# TEST-MODULE.net
KiCad netlist of a schematic drawn in Altium Designer
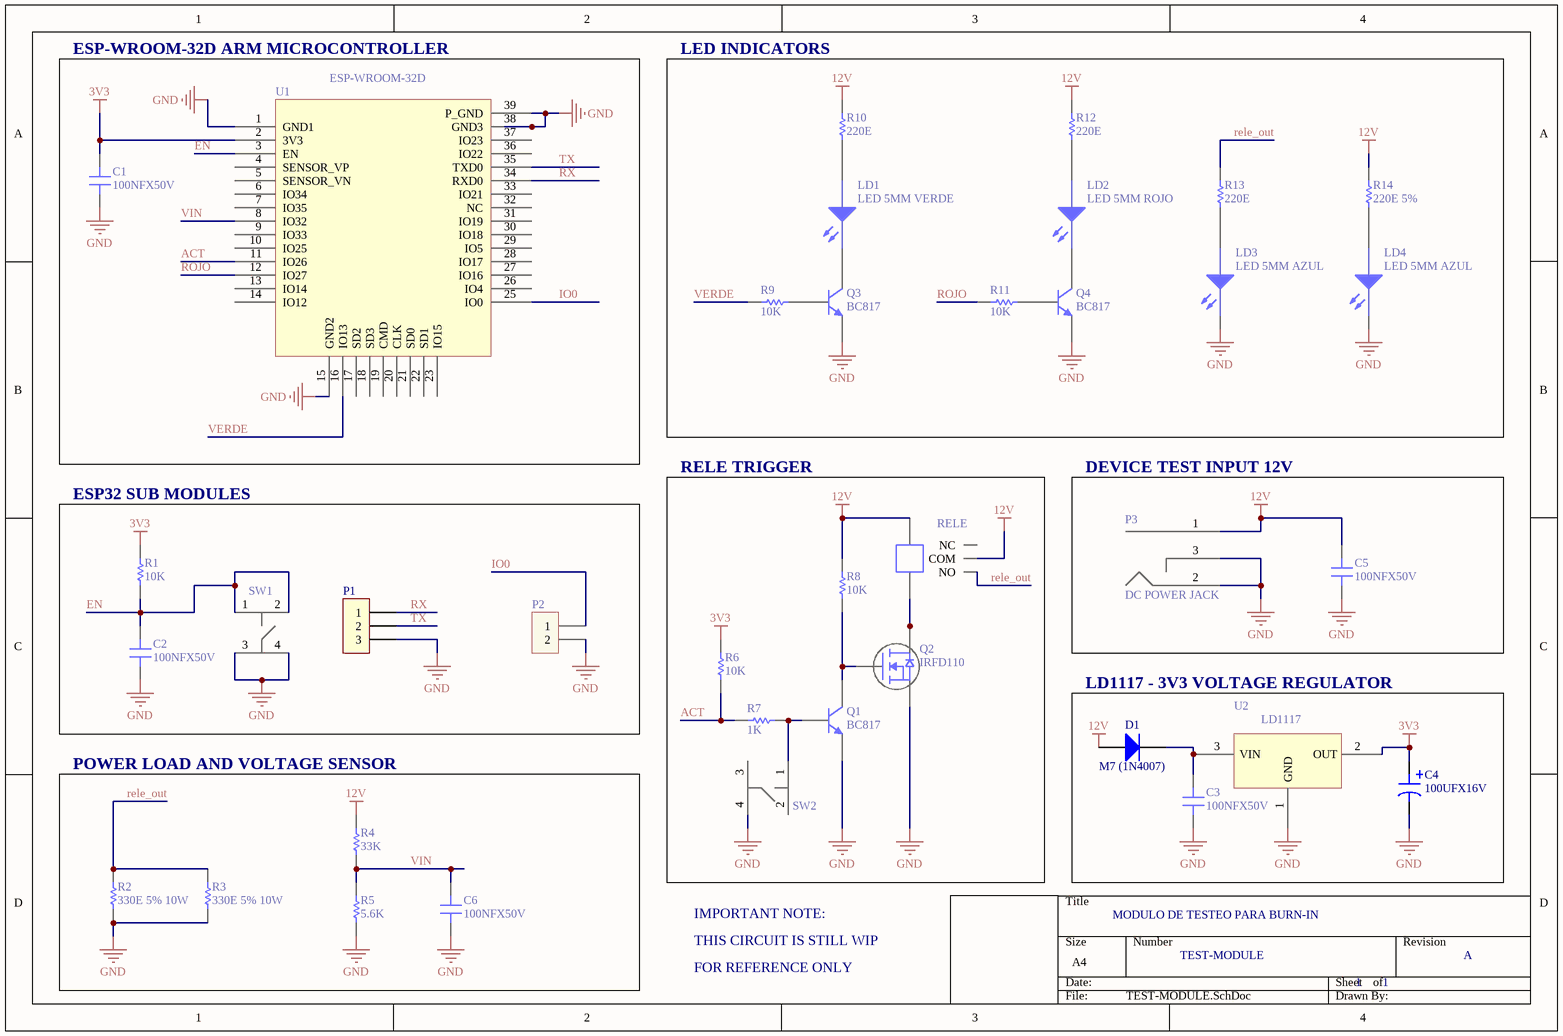
[diagram p0: TEST-MODULE.SchDoc]

(export (version "E")
  (design (tool "Eeschema 10.0.6"))
  (components
    (comp (ref "C1")
      (value "100NFX50V")
      (footprint "CAP.SMD.0805")
      (description "100NFX50V X7R 10% CER.MULT. SMD 0805")
      (libsource (lib "Libreria-Capacitores") (part "Capacitor 100NFX50V X7R 10% CER.MULT. SMD 0805"))
    )
    (comp (ref "C2")
      (value "100NFX50V")
      (footprint "CAP.SMD.0805")
      (description "100NFX50V X7R 10% CER.MULT. SMD 0805")
      (libsource (lib "Libreria-Capacitores") (part "Capacitor 100NFX50V X7R 10% CER.MULT. SMD 0805"))
    )
    (comp (ref "C3")
      (value "100NFX50V")
      (footprint "CAP.SMD.0805")
      (description "100NFX50V X7R 10% CER.MULT. SMD 0805")
      (libsource (lib "Libreria-Capacitores") (part "Capacitor 100NFX50V X7R 10% CER.MULT. SMD 0805"))
    )
    (comp (ref "C4")
      (value "100UFX16V")
      (footprint "CAP-ELEC-SMD")
      (description "100UFX16V 20%. 6.3x5.3 ELE.RAD.SMD [R=]")
      (libsource (lib "Libreria-Capacitores") (part "Capacitor Electrolitico SMD 100UFX16V 20%. 6.3x5.3 ELE.RAD.SMD [R=]"))
    )
    (comp (ref "C5")
      (value "100NFX50V")
      (footprint "CAP.SMD.0805")
      (description "100NFX50V X7R 10% CER.MULT. SMD 0805")
      (libsource (lib "Libreria-Capacitores") (part "Capacitor 100NFX50V X7R 10% CER.MULT. SMD 0805"))
    )
    (comp (ref "C6")
      (value "100NFX50V")
      (footprint "CAP.SMD.0805")
      (description "100NFX50V X7R 10% CER.MULT. SMD 0805")
      (libsource (lib "Libreria-Capacitores") (part "Capacitor 100NFX50V X7R 10% CER.MULT. SMD 0805"))
    )
    (comp (ref "D1")
      (value "M7 (1N4007)")
      (footprint "Diode-SMD-SMA")
      (description "M7 DIODO 1A 1000V SMD-SMA (1N4007) XYG")
      (libsource (lib "Libreria-Diodos") (part "Diodo M7 DIODO 1A 1000V SMD-SMA (1N4007) XYG"))
    )
    (comp (ref "LD1")
      (value "LED 5MM VERDE")
      (footprint "LED-5MM-ALTO-9-VERDE")
      (description "LED 5MM VERDE ALTO 9")
      (libsource (lib "Libreria-LEDs") (part "LED 5MM VERDE ALTO 9"))
    )
    (comp (ref "LD2")
      (value "LED 5MM ROJO")
      (footprint "LED-5MM-ALTO-9-ROJO")
      (description "LED 5MM ROJO ALTO 9")
      (libsource (lib "Libreria-LEDs") (part "LED 5MM ROJO ALTO 9"))
    )
    (comp (ref "LD3")
      (value "LED 5MM AZUL")
      (footprint "LED-5MM-ALTO-9-AZUL")
      (description "LED 5MM AZUL ALTO 9")
      (libsource (lib "Libreria-LEDs") (part "LED 5MM AZUL ALTO 9"))
    )
    (comp (ref "LD4")
      (value "LED 5MM AZUL")
      (footprint "LED-5MM-ALTO-9-AZUL")
      (description "LED 5MM AZUL ALTO 9")
      (libsource (lib "Libreria-LEDs") (part "LED 5MM AZUL ALTO 9"))
    )
    (comp (ref "P1")
      (value "IDC-MA-THT-1X3-P2.54MM-L11")
      (footprint "IDC-MA-THT-1X3-P2.54MM-L11")
      (libsource (lib "Libreria-Conectores") (part "IDC-MA-THT-1X3-P2.54MM-L11"))
    )
    (comp (ref "P2")
      (value "IDC-MA-THT-1X2-P2.54MM-L11")
      (footprint "IDC-MA-THT-1X2-P2.54MM-L11")
      (libsource (lib "Libreria-Conectores") (part "IDC-MA-THT-1X2-P2.54MM-L11"))
    )
    (comp (ref "P3")
      (value "DC POWER JACK")
      (footprint "VAR-DC-JACK - VERT")
      (description "DC POWER JACK VERTICAL 2MM")
      (libsource (lib "Libreria-Varios") (part "DC POWER JACK VERTICAL 2MM"))
    )
    (comp (ref "Q1")
      (value "BC817")
      (footprint "NPN.SMD.SOT23")
      (description "BC817-40 TRA.NPN 45V0.5A 0.25W SOT23")
      (libsource (lib "Libreria-Transistores") (part "Transistor BC817-40 TRA.NPN 45V0.5A 0.25W SOT23"))
    )
    (comp (ref "Q2")
      (value "IRFD110")
      (footprint "TRA-IRFD110")
      (description "Transistor MOSFET N IRFD110")
      (libsource (lib "Libreria-Transistores") (part "Transistor MOSFET N IRFD110"))
    )
    (comp (ref "Q3")
      (value "BC817")
      (footprint "NPN.SMD.SOT23")
      (description "BC817-40 TRA.NPN 45V0.5A 0.25W SOT23")
      (libsource (lib "Libreria-Transistores") (part "Transistor BC817-40 TRA.NPN 45V0.5A 0.25W SOT23"))
    )
    (comp (ref "Q4")
      (value "BC817")
      (footprint "NPN.SMD.SOT23")
      (description "BC817-40 TRA.NPN 45V0.5A 0.25W SOT23")
      (libsource (lib "Libreria-Transistores") (part "Transistor BC817-40 TRA.NPN 45V0.5A 0.25W SOT23"))
    )
    (comp (ref "R1")
      (value "10K")
      (footprint "RES.SMD.103")
      (description "10K 5% 0805 1/8W RES.SMD")
      (libsource (lib "Libreria-Resistencias") (part "Resistencia 10K 5% 0805 1/8W"))
    )
    (comp (ref "R2")
      (value "330E 5% 10W")
      (footprint "RES-CERAMICA-10W")
      (description "Resistencia Ceramica 330E 5% 10W SE15 RES.CEM")
      (libsource (lib "Libreria-Resistencias") (part "Resistencia Ceramica 330E 5% 10W SE15 RES.CEM"))
    )
    (comp (ref "R3")
      (value "330E 5% 10W")
      (footprint "RES-CERAMICA-10W")
      (description "Resistencia Ceramica 330E 5% 10W SE15 RES.CEM")
      (libsource (lib "Libreria-Resistencias") (part "Resistencia Ceramica 330E 5% 10W SE15 RES.CEM"))
    )
    (comp (ref "R4")
      (value "33K")
      (footprint "RES.SMD.333")
      (description "33K 5% 0805 1/8W RES.SMD")
      (libsource (lib "Libreria-Resistencias") (part "Resistencia 33K 5% 0805 1/8W"))
    )
    (comp (ref "R5")
      (value "5.6K")
      (footprint "RES.SMD.562")
      (description "5.6K 5% 0805 1/8W RES.SMD")
      (libsource (lib "Libreria-Resistencias") (part "Resistencia 5.6K 5% 0805 1/8W"))
    )
    (comp (ref "R6")
      (value "10K")
      (footprint "RES.SMD.103")
      (description "10K 5% 0805 1/8W RES.SMD")
      (libsource (lib "Libreria-Resistencias") (part "Resistencia 10K 5% 0805 1/8W"))
    )
    (comp (ref "R7")
      (value "1K")
      (footprint "RES.SMD.102")
      (description "1K 5% 0805 1/8W RES.SMD")
      (libsource (lib "Libreria-Resistencias") (part "Resistencia 1K 5% 0805 1/8W"))
    )
    (comp (ref "R8")
      (value "10K")
      (footprint "RES.SMD.103")
      (description "10K 5% 0805 1/8W RES.SMD")
      (libsource (lib "Libreria-Resistencias") (part "Resistencia 10K 5% 0805 1/8W"))
    )
    (comp (ref "R9")
      (value "10K")
      (footprint "RES.SMD.103")
      (description "10K 5% 0805 1/8W RES.SMD")
      (libsource (lib "Libreria-Resistencias") (part "Resistencia 10K 5% 0805 1/8W"))
    )
    (comp (ref "R10")
      (value "220E")
      (footprint "RES.SMD.221")
      (description "220E 5% 0805 1/8W RES.SMD")
      (libsource (lib "Libreria-Resistencias") (part "Resistencia 220E 5% 0805 1/8W"))
    )
    (comp (ref "R11")
      (value "10K")
      (footprint "RES.SMD.103")
      (description "10K 5% 0805 1/8W RES.SMD")
      (libsource (lib "Libreria-Resistencias") (part "Resistencia 10K 5% 0805 1/8W"))
    )
    (comp (ref "R12")
      (value "220E")
      (footprint "RES.SMD.221")
      (description "220E 5% 0805 1/8W RES.SMD")
      (libsource (lib "Libreria-Resistencias") (part "Resistencia 220E 5% 0805 1/8W"))
    )
    (comp (ref "R13")
      (value "220E")
      (footprint "RES.SMD.221")
      (description "220E 5% 0805 1/8W RES.SMD")
      (libsource (lib "Libreria-Resistencias") (part "Resistencia 220E 5% 0805 1/8W"))
    )
    (comp (ref "R14")
      (value "220E 5%")
      (footprint "RES.SMD.221")
      (description "220E 5% 0805 1/8W RES.SMD")
      (libsource (lib "Libreria-Resistencias") (part "Resistencia 220E 5% 0805 1/8W"))
    )
    (comp (ref "RELE")
      (value "Relay simple inversor 12V 12A")
      (footprint "RELAY 12V 12A CHICO")
      (libsource (lib "Libreria-Varios") (part "VAR-RELE-12V Relay simple inversor chico 12V 12A"))
    )
    (comp (ref "SW1")
      (value "TACT-SWITCH-THT-4C-06X06(5MM)")
      (footprint "TACT-SWITCH-THT-4C-06X06-5MM")
      (libsource (lib "Libreria-Switches") (part "TACT-SWITCH-THT-4C-06X06(5MM)"))
    )
    (comp (ref "SW2")
      (value "TACT-SWITCH-THT-4C-06X06(13MM)-JIANFU")
      (footprint "TACT-SWITCH-THT-4C-06X06-13MM")
      (libsource (lib "Libreria-Switches") (part "TACT-SWITCH-THT-4C-06X06(13MM)-JIANFU"))
    )
    (comp (ref "U1")
      (value "ESP32-WROOM-32D")
      (footprint "ESP32-WROOM-32D")
      (libsource (lib "Libreria-Semiconductores") (part "ESP32-WROOM-32D"))
    )
    (comp (ref "U2")
      (value "LD1117S33TR SMD DPAK 0.8A 3.3V LDO LINEAR REGULATOR")
      (footprint "DPAK")
      (libsource (lib "Libreria-Semiconductores") (part "LD1117S33TR SMD DPAK 0.8A 3.3V LDO LINEAR REGULATOR"))
    )
  )
  (nets
    (net (code "1") (name "/ACT") (class "Default")
      (node (ref "R6") (pin "1") (pinfunction "1_1") (pintype "passive"))
      (node (ref "R7") (pin "1") (pinfunction "1_1") (pintype "passive"))
      (node (ref "U1") (pin "11") (pinfunction "IO26_11") (pintype "passive"))
    )
    (net (code "2") (name "/EN") (class "Default")
      (node (ref "C2") (pin "2") (pinfunction "2_2") (pintype "passive"))
      (node (ref "R1") (pin "1") (pinfunction "1_1") (pintype "passive"))
      (node (ref "SW1") (pin "1") (pinfunction "1_1") (pintype "passive"))
      (node (ref "SW1") (pin "2") (pinfunction "2_2") (pintype "passive"))
      (node (ref "U1") (pin "3") (pinfunction "EN_3") (pintype "passive"))
    )
    (net (code "3") (name "/IO0") (class "Default")
      (node (ref "P2") (pin "1") (pinfunction "1_1") (pintype "passive"))
      (node (ref "U1") (pin "25") (pinfunction "IO0_25") (pintype "passive"))
    )
    (net (code "4") (name "/ROJO") (class "Default")
      (node (ref "R11") (pin "2") (pinfunction "2_2") (pintype "passive"))
      (node (ref "U1") (pin "12") (pinfunction "IO27_12") (pintype "passive"))
    )
    (net (code "5") (name "/RX") (class "Default")
      (node (ref "P1") (pin "1") (pinfunction "1_1") (pintype "passive"))
      (node (ref "U1") (pin "34") (pinfunction "RXD0_34") (pintype "passive"))
    )
    (net (code "6") (name "/TX") (class "Default")
      (node (ref "P1") (pin "2") (pinfunction "2_2") (pintype "passive"))
      (node (ref "U1") (pin "35") (pinfunction "TXD0_35") (pintype "passive"))
    )
    (net (code "7") (name "/VERDE") (class "Default")
      (node (ref "R9") (pin "1") (pinfunction "1_1") (pintype "passive"))
      (node (ref "U1") (pin "16") (pinfunction "IO13_16") (pintype "passive"))
    )
    (net (code "8") (name "/VIN") (class "Default")
      (node (ref "C6") (pin "2") (pinfunction "2_2") (pintype "passive"))
      (node (ref "R4") (pin "1") (pinfunction "1_1") (pintype "passive"))
      (node (ref "R5") (pin "2") (pinfunction "2_2") (pintype "passive"))
      (node (ref "U1") (pin "8") (pinfunction "IO32_8") (pintype "passive"))
    )
    (net (code "9") (name "/rele_out") (class "Default")
      (node (ref "R13") (pin "2") (pinfunction "2_2") (pintype "passive"))
      (node (ref "R2") (pin "2") (pinfunction "2_2") (pintype "passive"))
      (node (ref "R3") (pin "2") (pinfunction "2_2") (pintype "passive"))
      (node (ref "RELE") (pin "4") (pinfunction "NO_4") (pintype "passive"))
    )
    (net (code "10") (name "3V3") (class "Default")
      (node (ref "C1") (pin "2") (pinfunction "2_2") (pintype "passive"))
      (node (ref "C4") (pin "2") (pinfunction "2_2") (pintype "passive"))
      (node (ref "R1") (pin "2") (pinfunction "2_2") (pintype "passive"))
      (node (ref "R6") (pin "2") (pinfunction "2_2") (pintype "passive"))
      (node (ref "U1") (pin "2") (pinfunction "3V3_2") (pintype "passive"))
      (node (ref "U2") (pin "2") (pinfunction "OUT_2") (pintype "passive"))
    )
    (net (code "11") (name "12V") (class "Default")
      (node (ref "C5") (pin "2") (pinfunction "2_2") (pintype "passive"))
      (node (ref "D1") (pin "A") (pinfunction "A_A") (pintype "passive"))
      (node (ref "P3") (pin "1") (pinfunction "1_1") (pintype "passive"))
      (node (ref "R10") (pin "2") (pinfunction "2_2") (pintype "passive"))
      (node (ref "R12") (pin "2") (pinfunction "2_2") (pintype "passive"))
      (node (ref "R14") (pin "2") (pinfunction "2_2") (pintype "passive"))
      (node (ref "R4") (pin "2") (pinfunction "2_2") (pintype "passive"))
      (node (ref "R8") (pin "2") (pinfunction "2_2") (pintype "passive"))
      (node (ref "RELE") (pin "1") (pinfunction "1_1") (pintype "passive"))
      (node (ref "RELE") (pin "3") (pinfunction "COM_3") (pintype "passive"))
    )
    (net (code "12") (name "GND") (class "Default")
      (node (ref "C1") (pin "1") (pinfunction "1_1") (pintype "passive"))
      (node (ref "C2") (pin "1") (pinfunction "1_1") (pintype "passive"))
      (node (ref "C3") (pin "1") (pinfunction "1_1") (pintype "passive"))
      (node (ref "C4") (pin "1") (pinfunction "1_1") (pintype "passive"))
      (node (ref "C5") (pin "1") (pinfunction "1_1") (pintype "passive"))
      (node (ref "C6") (pin "1") (pinfunction "1_1") (pintype "passive"))
      (node (ref "LD3") (pin "K") (pinfunction "KB_K") (pintype "passive"))
      (node (ref "LD4") (pin "K") (pinfunction "KB_K") (pintype "passive"))
      (node (ref "P1") (pin "3") (pinfunction "3_3") (pintype "passive"))
      (node (ref "P2") (pin "2") (pinfunction "2_2") (pintype "passive"))
      (node (ref "P3") (pin "2") (pinfunction "2_2") (pintype "passive"))
      (node (ref "P3") (pin "3") (pinfunction "3_3") (pintype "passive"))
      (node (ref "Q1") (pin "2") (pinfunction "E_2") (pintype "passive"))
      (node (ref "Q2") (pin "4") (pinfunction "4_4") (pintype "passive"))
      (node (ref "Q3") (pin "2") (pinfunction "E_2") (pintype "passive"))
      (node (ref "Q4") (pin "2") (pinfunction "E_2") (pintype "passive"))
      (node (ref "R2") (pin "1") (pinfunction "1_1") (pintype "passive"))
      (node (ref "R3") (pin "1") (pinfunction "1_1") (pintype "passive"))
      (node (ref "R5") (pin "1") (pinfunction "1_1") (pintype "passive"))
      (node (ref "SW1") (pin "3") (pinfunction "3_3") (pintype "passive"))
      (node (ref "SW1") (pin "4") (pinfunction "4_4") (pintype "passive"))
      (node (ref "SW2") (pin "4") (pinfunction "4_4") (pintype "passive"))
      (node (ref "U1") (pin "1") (pinfunction "GND1_1") (pintype "passive"))
      (node (ref "U1") (pin "15") (pinfunction "GND2_15") (pintype "passive"))
      (node (ref "U1") (pin "38") (pinfunction "GND3_38") (pintype "passive"))
      (node (ref "U1") (pin "39") (pinfunction "P_GND_39") (pintype "passive"))
      (node (ref "U2") (pin "1") (pinfunction "GND_1") (pintype "passive"))
    )
    (net (code "13") (name "Net-(LD1-AB)") (class "Default")
      (node (ref "LD1") (pin "A") (pinfunction "AB_A") (pintype "passive"))
      (node (ref "R10") (pin "1") (pinfunction "1_1") (pintype "passive"))
    )
    (net (code "14") (name "Net-(LD1-KB)") (class "Default")
      (node (ref "LD1") (pin "K") (pinfunction "KB_K") (pintype "passive"))
      (node (ref "Q3") (pin "3") (pinfunction "C_3") (pintype "passive"))
    )
    (net (code "15") (name "Net-(LD2-AB)") (class "Default")
      (node (ref "LD2") (pin "A") (pinfunction "AB_A") (pintype "passive"))
      (node (ref "R12") (pin "1") (pinfunction "1_1") (pintype "passive"))
    )
    (net (code "16") (name "Net-(LD2-KB)") (class "Default")
      (node (ref "LD2") (pin "K") (pinfunction "KB_K") (pintype "passive"))
      (node (ref "Q4") (pin "3") (pinfunction "C_3") (pintype "passive"))
    )
    (net (code "17") (name "Net-(LD3-AB)") (class "Default")
      (node (ref "LD3") (pin "A") (pinfunction "AB_A") (pintype "passive"))
      (node (ref "R13") (pin "1") (pinfunction "1_1") (pintype "passive"))
    )
    (net (code "18") (name "Net-(LD4-AB)") (class "Default")
      (node (ref "LD4") (pin "A") (pinfunction "AB_A") (pintype "passive"))
      (node (ref "R14") (pin "1") (pinfunction "1_1") (pintype "passive"))
    )
    (net (code "19") (name "Net-(Q1-B)") (class "Default")
      (node (ref "Q1") (pin "1") (pinfunction "B_1") (pintype "passive"))
      (node (ref "R7") (pin "2") (pinfunction "2_2") (pintype "passive"))
      (node (ref "SW2") (pin "1") (pinfunction "1_1") (pintype "passive"))
    )
    (net (code "20") (name "Net-(Q1-C)") (class "Default")
      (node (ref "Q1") (pin "3") (pinfunction "C_3") (pintype "passive"))
      (node (ref "Q2") (pin "3") (pinfunction "3_3") (pintype "passive"))
      (node (ref "R8") (pin "1") (pinfunction "1_1") (pintype "passive"))
    )
    (net (code "21") (name "Net-(Q2-Pad1)") (class "Default")
      (node (ref "Q2") (pin "1") (pinfunction "1_1") (pintype "passive"))
      (node (ref "Q2") (pin "2") (pinfunction "2_2") (pintype "passive"))
      (node (ref "RELE") (pin "2") (pinfunction "2_2") (pintype "passive"))
    )
    (net (code "22") (name "Net-(Q3-B)") (class "Default")
      (node (ref "Q3") (pin "1") (pinfunction "B_1") (pintype "passive"))
      (node (ref "R9") (pin "2") (pinfunction "2_2") (pintype "passive"))
    )
    (net (code "23") (name "Net-(Q4-B)") (class "Default")
      (node (ref "Q4") (pin "1") (pinfunction "B_1") (pintype "passive"))
      (node (ref "R11") (pin "1") (pinfunction "1_1") (pintype "passive"))
    )
    (net (code "24") (name "Net-(U2-VIN)") (class "Default")
      (node (ref "C3") (pin "2") (pinfunction "2_2") (pintype "passive"))
      (node (ref "D1") (pin "K") (pinfunction "K_K") (pintype "passive"))
      (node (ref "U2") (pin "3") (pinfunction "VIN_3") (pintype "passive"))
    )
    (net (code "25") (name "unconnected-(RELE-NC-Pad5)") (class "Default")
      (node (ref "RELE") (pin "5") (pinfunction "NC_5") (pintype "passive"))
    )
    (net (code "26") (name "unconnected-(SW2-Pad2)") (class "Default")
      (node (ref "SW2") (pin "2") (pinfunction "2_2") (pintype "passive"))
    )
    (net (code "27") (name "unconnected-(SW2-Pad3)") (class "Default")
      (node (ref "SW2") (pin "3") (pinfunction "3_3") (pintype "passive"))
    )
    (net (code "28") (name "unconnected-(U1-CLK-Pad20)") (class "Default")
      (node (ref "U1") (pin "20") (pinfunction "CLK_20") (pintype "passive"))
    )
    (net (code "29") (name "unconnected-(U1-CMD-Pad19)") (class "Default")
      (node (ref "U1") (pin "19") (pinfunction "CMD_19") (pintype "passive"))
    )
    (net (code "30") (name "unconnected-(U1-IO4-Pad26)") (class "Default")
      (node (ref "U1") (pin "26") (pinfunction "IO4_26") (pintype "passive"))
    )
    (net (code "31") (name "unconnected-(U1-IO5-Pad29)") (class "Default")
      (node (ref "U1") (pin "29") (pinfunction "IO5_29") (pintype "passive"))
    )
    (net (code "32") (name "unconnected-(U1-IO12-Pad14)") (class "Default")
      (node (ref "U1") (pin "14") (pinfunction "IO12_14") (pintype "passive"))
    )
    (net (code "33") (name "unconnected-(U1-IO14-Pad13)") (class "Default")
      (node (ref "U1") (pin "13") (pinfunction "IO14_13") (pintype "passive"))
    )
    (net (code "34") (name "unconnected-(U1-IO15-Pad23)") (class "Default")
      (node (ref "U1") (pin "23") (pinfunction "IO15_23") (pintype "passive"))
    )
    (net (code "35") (name "unconnected-(U1-IO16-Pad27)") (class "Default")
      (node (ref "U1") (pin "27") (pinfunction "IO16_27") (pintype "passive"))
    )
    (net (code "36") (name "unconnected-(U1-IO17-Pad28)") (class "Default")
      (node (ref "U1") (pin "28") (pinfunction "IO17_28") (pintype "passive"))
    )
    (net (code "37") (name "unconnected-(U1-IO18-Pad30)") (class "Default")
      (node (ref "U1") (pin "30") (pinfunction "IO18_30") (pintype "passive"))
    )
    (net (code "38") (name "unconnected-(U1-IO19-Pad31)") (class "Default")
      (node (ref "U1") (pin "31") (pinfunction "IO19_31") (pintype "passive"))
    )
    (net (code "39") (name "unconnected-(U1-IO21-Pad33)") (class "Default")
      (node (ref "U1") (pin "33") (pinfunction "IO21_33") (pintype "passive"))
    )
    (net (code "40") (name "unconnected-(U1-IO22-Pad36)") (class "Default")
      (node (ref "U1") (pin "36") (pinfunction "IO22_36") (pintype "passive"))
    )
    (net (code "41") (name "unconnected-(U1-IO23-Pad37)") (class "Default")
      (node (ref "U1") (pin "37") (pinfunction "IO23_37") (pintype "passive"))
    )
    (net (code "42") (name "unconnected-(U1-IO25-Pad10)") (class "Default")
      (node (ref "U1") (pin "10") (pinfunction "IO25_10") (pintype "passive"))
    )
    (net (code "43") (name "unconnected-(U1-IO33-Pad9)") (class "Default")
      (node (ref "U1") (pin "9") (pinfunction "IO33_9") (pintype "passive"))
    )
    (net (code "44") (name "unconnected-(U1-IO34-Pad6)") (class "Default")
      (node (ref "U1") (pin "6") (pinfunction "IO34_6") (pintype "passive"))
    )
    (net (code "45") (name "unconnected-(U1-IO35-Pad7)") (class "Default")
      (node (ref "U1") (pin "7") (pinfunction "IO35_7") (pintype "passive"))
    )
    (net (code "46") (name "unconnected-(U1-NC-Pad32)") (class "Default")
      (node (ref "U1") (pin "32") (pinfunction "NC_32") (pintype "passive"))
    )
    (net (code "47") (name "unconnected-(U1-SD0-Pad21)") (class "Default")
      (node (ref "U1") (pin "21") (pinfunction "SD0_21") (pintype "passive"))
    )
    (net (code "48") (name "unconnected-(U1-SD1-Pad22)") (class "Default")
      (node (ref "U1") (pin "22") (pinfunction "SD1_22") (pintype "passive"))
    )
    (net (code "49") (name "unconnected-(U1-SD2-Pad17)") (class "Default")
      (node (ref "U1") (pin "17") (pinfunction "SD2_17") (pintype "passive"))
    )
    (net (code "50") (name "unconnected-(U1-SD3-Pad18)") (class "Default")
      (node (ref "U1") (pin "18") (pinfunction "SD3_18") (pintype "passive"))
    )
    (net (code "51") (name "unconnected-(U1-SENSOR_VN-Pad5)") (class "Default")
      (node (ref "U1") (pin "5") (pinfunction "SENSOR_VN_5") (pintype "passive"))
    )
    (net (code "52") (name "unconnected-(U1-SENSOR_VP-Pad4)") (class "Default")
      (node (ref "U1") (pin "4") (pinfunction "SENSOR_VP_4") (pintype "passive"))
    )
  )
)
